# Xbee-ATmega.net
KiCad netlist of a schematic drawn in EAGLE
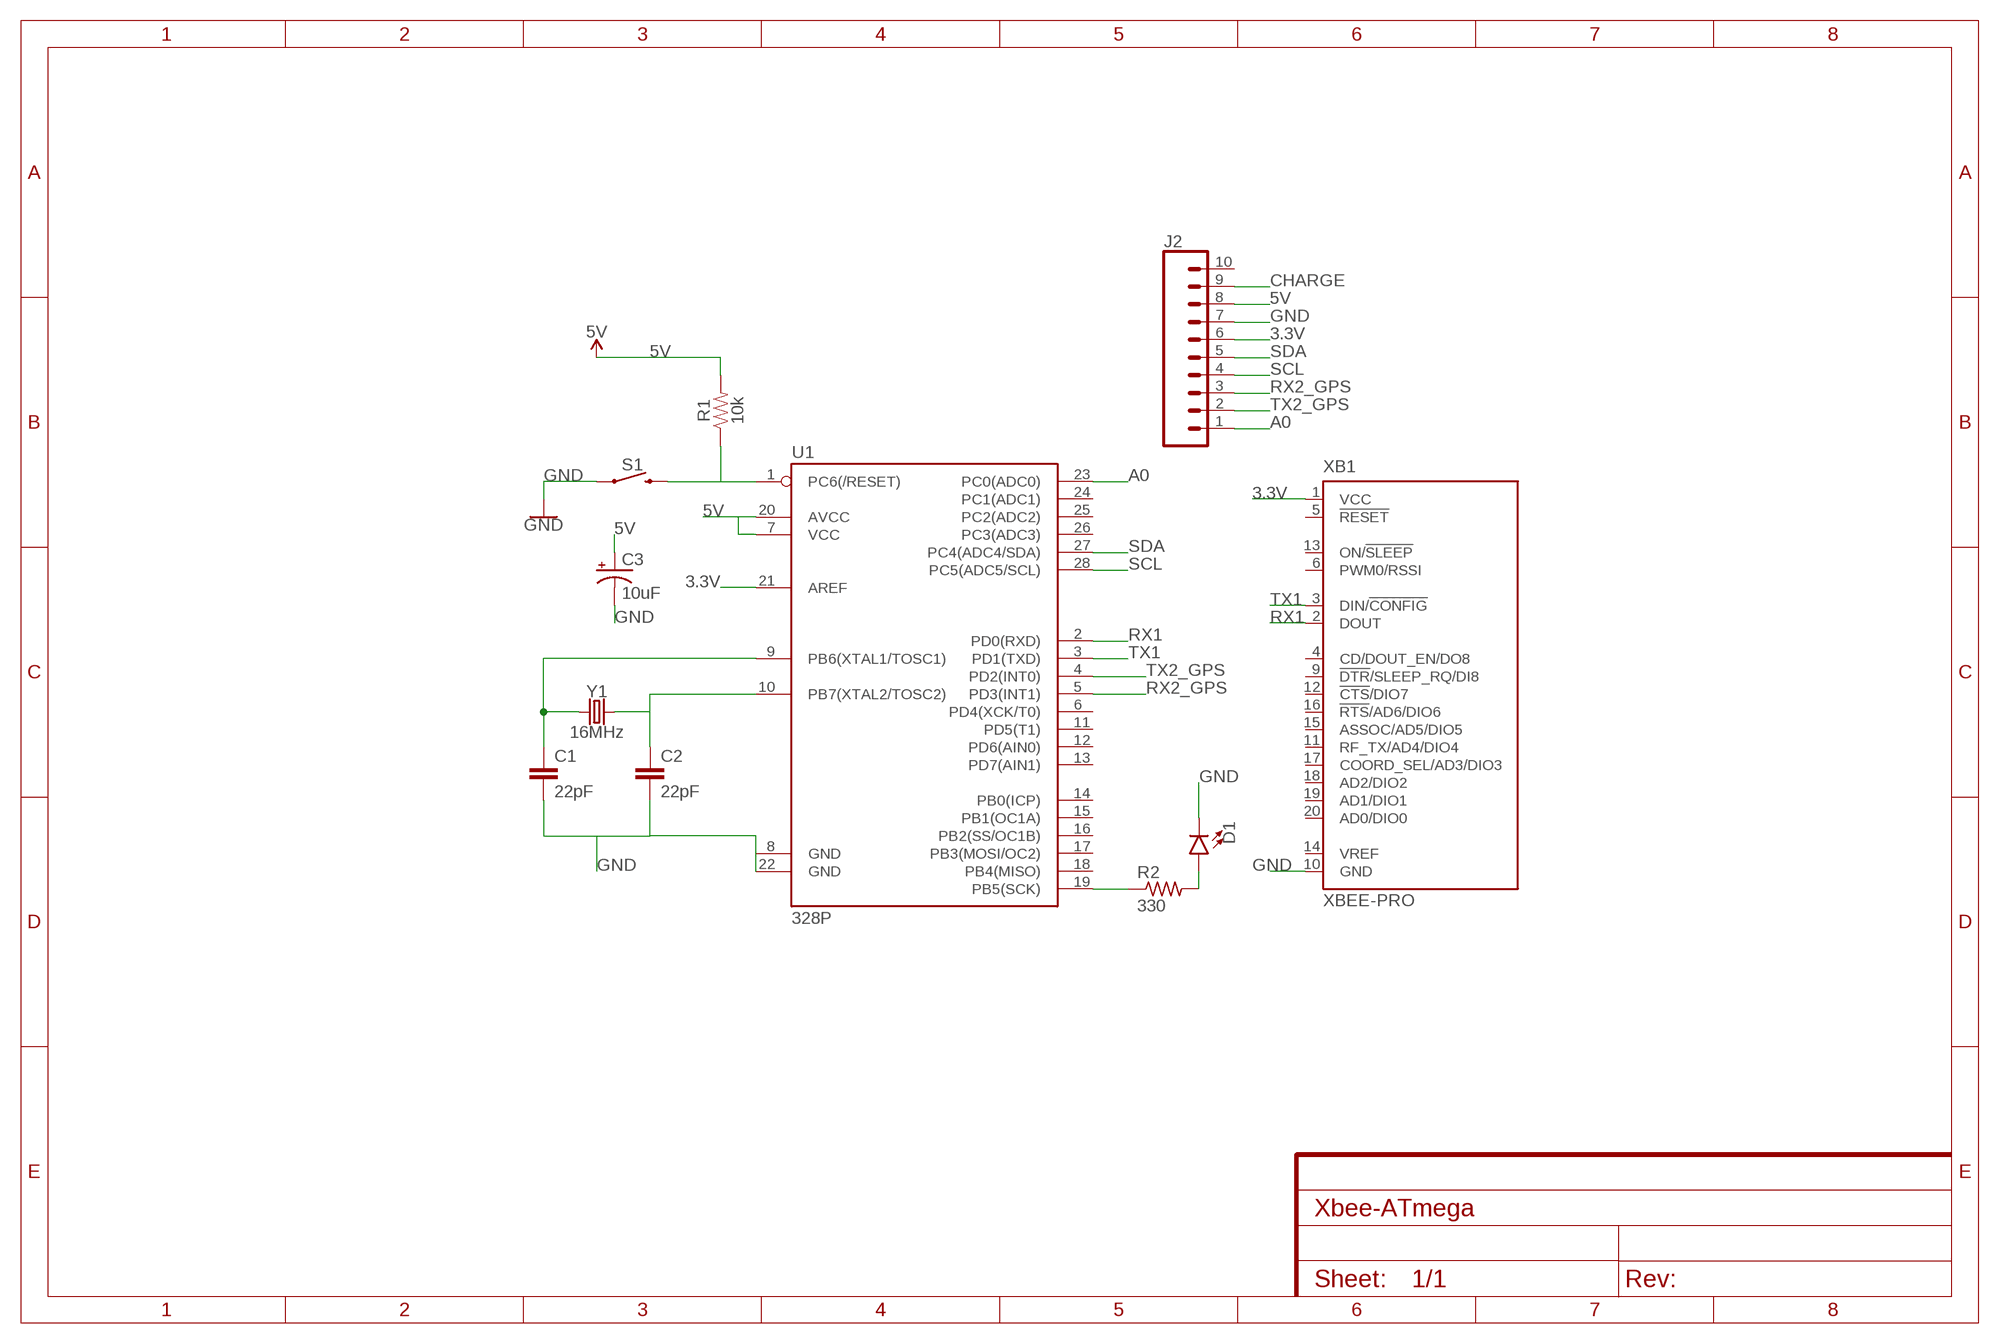
[diagram p0: schematic, sheet 1]

(export (version "E")
  (design (tool "Eeschema 10.0.6"))
  (components
    (comp (ref "C1")
      (value "22pF")
      (footprint "eagle-import:CAP-PTH-2.54")
      (libsource (lib "eagle-import") (part "22PF-PTH-2.54MM-200V-5%"))
    )
    (comp (ref "C2")
      (value "22pF")
      (footprint "eagle-import:CAP-PTH-2.54")
      (libsource (lib "eagle-import") (part "22PF-PTH-2.54MM-200V-5%"))
    )
    (comp (ref "C3")
      (value "10uF")
      (footprint "eagle-import:CPOL-RADIAL-2.5MM-5MM")
      (libsource (lib "eagle-import") (part "10UF-POLAR-RADIAL-2.5MM-25V-20%"))
    )
    (comp (ref "D1")
      (value "LED5MM")
      (footprint "eagle-import:LED_5MM")
      (libsource (lib "eagle-import") (part "LED5MM"))
    )
    (comp (ref "J2")
      (value "CONN_10\"")
      (footprint "eagle-import:1X10")
      (libsource (lib "eagle-import") (part "CONN_10{dblquote}"))
    )
    (comp (ref "R1")
      (value "10k")
      (footprint "eagle-import:AXIAL-0.3")
      (libsource (lib "eagle-import") (part "10KOHM-HORIZ-1/4W-1%"))
    )
    (comp (ref "R2")
      (value "330")
      (footprint "eagle-import:0207_7")
      (libsource (lib "eagle-import") (part "R-US_0207/7"))
    )
    (comp (ref "S1")
      (value "MOMENTARY-SWITCH-SPST-PTH-6.0MM")
      (footprint "eagle-import:TACTILE_SWITCH_PTH_6.0MM")
      (libsource (lib "eagle-import") (part "MOMENTARY-SWITCH-SPST-PTH-6.0MM"))
    )
    (comp (ref "U1")
      (value "328P")
      (footprint "eagle-import:DIP28")
      (libsource (lib "eagle-import") (part "ATMEGA328P_PDIP"))
    )
    (comp (ref "XB1")
      (value "XBEE-PRO")
      (footprint "eagle-import:XBEE-PRO")
      (fields (field (name "MPN") "XBP24-AWI-001"))
      (libsource (lib "eagle-import") (part "XBEE-PRO"))
    )
    (comp (ref "Y1")
      (value "16MHz")
      (footprint "eagle-import:HC49US")
      (libsource (lib "eagle-import") (part "CRYSTAL-16MHZPTH-HC49US"))
    )
  )
  (nets
    (net (code "1") (name "/3.3V") (class "Default")
      (node (ref "J2") (pin "6") (pinfunction "6_6") (pintype "passive"))
      (node (ref "U1") (pin "21") (pinfunction "AREF_21") (pintype "bidirectional"))
      (node (ref "XB1") (pin "1") (pinfunction "VCC_1") (pintype "power_in"))
    )
    (net (code "2") (name "/A0") (class "Default")
      (node (ref "J2") (pin "1") (pinfunction "1_1") (pintype "passive"))
      (node (ref "U1") (pin "23") (pinfunction "PC0(ADC0)_23") (pintype "bidirectional"))
    )
    (net (code "3") (name "/CHARGE") (class "Default")
      (node (ref "J2") (pin "9") (pinfunction "9_9") (pintype "passive"))
    )
    (net (code "4") (name "/RX1") (class "Default")
      (node (ref "U1") (pin "2") (pinfunction "PD0(RXD)_2") (pintype "bidirectional"))
      (node (ref "XB1") (pin "2") (pinfunction "DOUT_2") (pintype "output"))
    )
    (net (code "5") (name "/RX2_GPS") (class "Default")
      (node (ref "J2") (pin "3") (pinfunction "3_3") (pintype "passive"))
      (node (ref "U1") (pin "5") (pinfunction "PD3(INT1)_5") (pintype "bidirectional"))
    )
    (net (code "6") (name "/SCL") (class "Default")
      (node (ref "J2") (pin "4") (pinfunction "4_4") (pintype "passive"))
      (node (ref "U1") (pin "28") (pinfunction "PC5(ADC5/SCL)_28") (pintype "bidirectional"))
    )
    (net (code "7") (name "/SDA") (class "Default")
      (node (ref "J2") (pin "5") (pinfunction "5_5") (pintype "passive"))
      (node (ref "U1") (pin "27") (pinfunction "PC4(ADC4/SDA)_27") (pintype "bidirectional"))
    )
    (net (code "8") (name "/TX1") (class "Default")
      (node (ref "U1") (pin "3") (pinfunction "PD1(TXD)_3") (pintype "bidirectional"))
      (node (ref "XB1") (pin "3") (pinfunction "DIN/~{CONFIG}_3") (pintype "input"))
    )
    (net (code "9") (name "/TX2_GPS") (class "Default")
      (node (ref "J2") (pin "2") (pinfunction "2_2") (pintype "passive"))
      (node (ref "U1") (pin "4") (pinfunction "PD2(INT0)_4") (pintype "bidirectional"))
    )
    (net (code "10") (name "5V") (class "Default")
      (node (ref "C3") (pin "1") (pinfunction "+_1") (pintype "passive"))
      (node (ref "J2") (pin "8") (pinfunction "8_8") (pintype "passive"))
      (node (ref "R1") (pin "P$2") (pinfunction "2_P$2") (pintype "passive"))
      (node (ref "U1") (pin "20") (pinfunction "AVCC_20") (pintype "bidirectional"))
      (node (ref "U1") (pin "7") (pinfunction "VCC_7") (pintype "bidirectional"))
    )
    (net (code "11") (name "GND") (class "Default")
      (node (ref "C1") (pin "2") (pinfunction "2_2") (pintype "passive"))
      (node (ref "C2") (pin "2") (pinfunction "2_2") (pintype "passive"))
      (node (ref "C3") (pin "2") (pinfunction "-_2") (pintype "passive"))
      (node (ref "D1") (pin "K") (pinfunction "C_K") (pintype "passive"))
      (node (ref "J2") (pin "7") (pinfunction "7_7") (pintype "passive"))
      (node (ref "S1") (pin "1") (pinfunction "1_1") (pintype "passive"))
      (node (ref "U1") (pin "22") (pinfunction "GND_22") (pintype "bidirectional"))
      (node (ref "U1") (pin "8") (pinfunction "GND_8") (pintype "bidirectional"))
      (node (ref "XB1") (pin "10") (pinfunction "GND_10") (pintype "power_in"))
    )
    (net (code "12") (name "Net-(D1-PadA)") (class "Default")
      (node (ref "D1") (pin "A") (pinfunction "A_A") (pintype "passive"))
      (node (ref "R2") (pin "2") (pinfunction "2_2") (pintype "passive"))
    )
    (net (code "13") (name "Net-(R1-1)") (class "Default")
      (node (ref "R1") (pin "P$1") (pinfunction "1_P$1") (pintype "passive"))
      (node (ref "S1") (pin "3") (pinfunction "2_3") (pintype "passive"))
      (node (ref "U1") (pin "1") (pinfunction "PC6(/RESET)_1") (pintype "bidirectional"))
    )
    (net (code "14") (name "Net-(U1-PB5(SCK))") (class "Default")
      (node (ref "R2") (pin "1") (pinfunction "1_1") (pintype "passive"))
      (node (ref "U1") (pin "19") (pinfunction "PB5(SCK)_19") (pintype "bidirectional"))
    )
    (net (code "15") (name "Net-(U1-PB6(XTAL1{slash}TOSC1))") (class "Default")
      (node (ref "C1") (pin "1") (pinfunction "1_1") (pintype "passive"))
      (node (ref "U1") (pin "9") (pinfunction "PB6(XTAL1/TOSC1)_9") (pintype "bidirectional"))
      (node (ref "Y1") (pin "1") (pinfunction "1_1") (pintype "passive"))
    )
    (net (code "16") (name "Net-(U1-PB7(XTAL2{slash}TOSC2))") (class "Default")
      (node (ref "C2") (pin "1") (pinfunction "1_1") (pintype "passive"))
      (node (ref "U1") (pin "10") (pinfunction "PB7(XTAL2/TOSC2)_10") (pintype "bidirectional"))
      (node (ref "Y1") (pin "2") (pinfunction "2_2") (pintype "passive"))
    )
    (net (code "17") (name "unconnected-(J2-Pad10)") (class "Default")
      (node (ref "J2") (pin "10") (pinfunction "10_10") (pintype "passive"))
    )
    (net (code "18") (name "unconnected-(U1-PB0(ICP)-Pad14)") (class "Default")
      (node (ref "U1") (pin "14") (pinfunction "PB0(ICP)_14") (pintype "bidirectional"))
    )
    (net (code "19") (name "unconnected-(U1-PB1(OC1A)-Pad15)") (class "Default")
      (node (ref "U1") (pin "15") (pinfunction "PB1(OC1A)_15") (pintype "bidirectional"))
    )
    (net (code "20") (name "unconnected-(U1-PB2(SS{slash}OC1B)-Pad16)") (class "Default")
      (node (ref "U1") (pin "16") (pinfunction "PB2(SS/OC1B)_16") (pintype "bidirectional"))
    )
    (net (code "21") (name "unconnected-(U1-PB3(MOSI{slash}OC2)-Pad17)") (class "Default")
      (node (ref "U1") (pin "17") (pinfunction "PB3(MOSI/OC2)_17") (pintype "bidirectional"))
    )
    (net (code "22") (name "unconnected-(U1-PB4(MISO)-Pad18)") (class "Default")
      (node (ref "U1") (pin "18") (pinfunction "PB4(MISO)_18") (pintype "bidirectional"))
    )
    (net (code "23") (name "unconnected-(U1-PC1(ADC1)-Pad24)") (class "Default")
      (node (ref "U1") (pin "24") (pinfunction "PC1(ADC1)_24") (pintype "bidirectional"))
    )
    (net (code "24") (name "unconnected-(U1-PC2(ADC2)-Pad25)") (class "Default")
      (node (ref "U1") (pin "25") (pinfunction "PC2(ADC2)_25") (pintype "bidirectional"))
    )
    (net (code "25") (name "unconnected-(U1-PC3(ADC3)-Pad26)") (class "Default")
      (node (ref "U1") (pin "26") (pinfunction "PC3(ADC3)_26") (pintype "bidirectional"))
    )
    (net (code "26") (name "unconnected-(U1-PD4(XCK{slash}T0)-Pad6)") (class "Default")
      (node (ref "U1") (pin "6") (pinfunction "PD4(XCK/T0)_6") (pintype "bidirectional"))
    )
    (net (code "27") (name "unconnected-(U1-PD5(T1)-Pad11)") (class "Default")
      (node (ref "U1") (pin "11") (pinfunction "PD5(T1)_11") (pintype "bidirectional"))
    )
    (net (code "28") (name "unconnected-(U1-PD6(AIN0)-Pad12)") (class "Default")
      (node (ref "U1") (pin "12") (pinfunction "PD6(AIN0)_12") (pintype "bidirectional"))
    )
    (net (code "29") (name "unconnected-(U1-PD7(AIN1)-Pad13)") (class "Default")
      (node (ref "U1") (pin "13") (pinfunction "PD7(AIN1)_13") (pintype "bidirectional"))
    )
    (net (code "30") (name "unconnected-(XB1-AD0{slash}DIO0-Pad20)") (class "Default")
      (node (ref "XB1") (pin "20") (pinfunction "AD0/DIO0_20") (pintype "bidirectional"))
    )
    (net (code "31") (name "unconnected-(XB1-AD1{slash}DIO1-Pad19)") (class "Default")
      (node (ref "XB1") (pin "19") (pinfunction "AD1/DIO1_19") (pintype "bidirectional"))
    )
    (net (code "32") (name "unconnected-(XB1-AD2{slash}DIO2-Pad18)") (class "Default")
      (node (ref "XB1") (pin "18") (pinfunction "AD2/DIO2_18") (pintype "bidirectional"))
    )
    (net (code "33") (name "unconnected-(XB1-ASSOC{slash}AD5{slash}DIO5-Pad15)") (class "Default")
      (node (ref "XB1") (pin "15") (pinfunction "ASSOC/AD5/DIO5_15") (pintype "bidirectional"))
    )
    (net (code "34") (name "unconnected-(XB1-CD{slash}DOUT_EN{slash}DO8-Pad4)") (class "Default")
      (node (ref "XB1") (pin "4") (pinfunction "CD/DOUT_EN/DO8_4") (pintype "output"))
    )
    (net (code "35") (name "unconnected-(XB1-COORD_SEL{slash}AD3{slash}DIO3-Pad17)") (class "Default")
      (node (ref "XB1") (pin "17") (pinfunction "COORD_SEL/AD3/DIO3_17") (pintype "bidirectional"))
    )
    (net (code "36") (name "unconnected-(XB1-ON{slash}~{SLEEP}-Pad13)") (class "Default")
      (node (ref "XB1") (pin "13") (pinfunction "ON/~{SLEEP}_13") (pintype "output"))
    )
    (net (code "37") (name "unconnected-(XB1-PWM0{slash}RSSI-Pad6)") (class "Default")
      (node (ref "XB1") (pin "6") (pinfunction "PWM0/RSSI_6") (pintype "output"))
    )
    (net (code "38") (name "unconnected-(XB1-RF_TX{slash}AD4{slash}DIO4-Pad11)") (class "Default")
      (node (ref "XB1") (pin "11") (pinfunction "RF_TX/AD4/DIO4_11") (pintype "bidirectional"))
    )
    (net (code "39") (name "unconnected-(XB1-VREF-Pad14)") (class "Default")
      (node (ref "XB1") (pin "14") (pinfunction "VREF_14") (pintype "input"))
    )
    (net (code "40") (name "unconnected-(XB1-~{CTS}{slash}DIO7-Pad12)") (class "Default")
      (node (ref "XB1") (pin "12") (pinfunction "~{CTS}/DIO7_12") (pintype "bidirectional"))
    )
    (net (code "41") (name "unconnected-(XB1-~{DTR}{slash}SLEEP_RQ{slash}DI8-Pad9)") (class "Default")
      (node (ref "XB1") (pin "9") (pinfunction "~{DTR}/SLEEP_RQ/DI8_9") (pintype "bidirectional"))
    )
    (net (code "42") (name "unconnected-(XB1-~{RESET}-Pad5)") (class "Default")
      (node (ref "XB1") (pin "5") (pinfunction "~{RESET}_5") (pintype "input"))
    )
    (net (code "43") (name "unconnected-(XB1-~{RTS}{slash}AD6{slash}DIO6-Pad16)") (class "Default")
      (node (ref "XB1") (pin "16") (pinfunction "~{RTS}/AD6/DIO6_16") (pintype "bidirectional"))
    )
  )
)
